# LEDs.net
KiCad netlist of a schematic drawn in Altium Designer
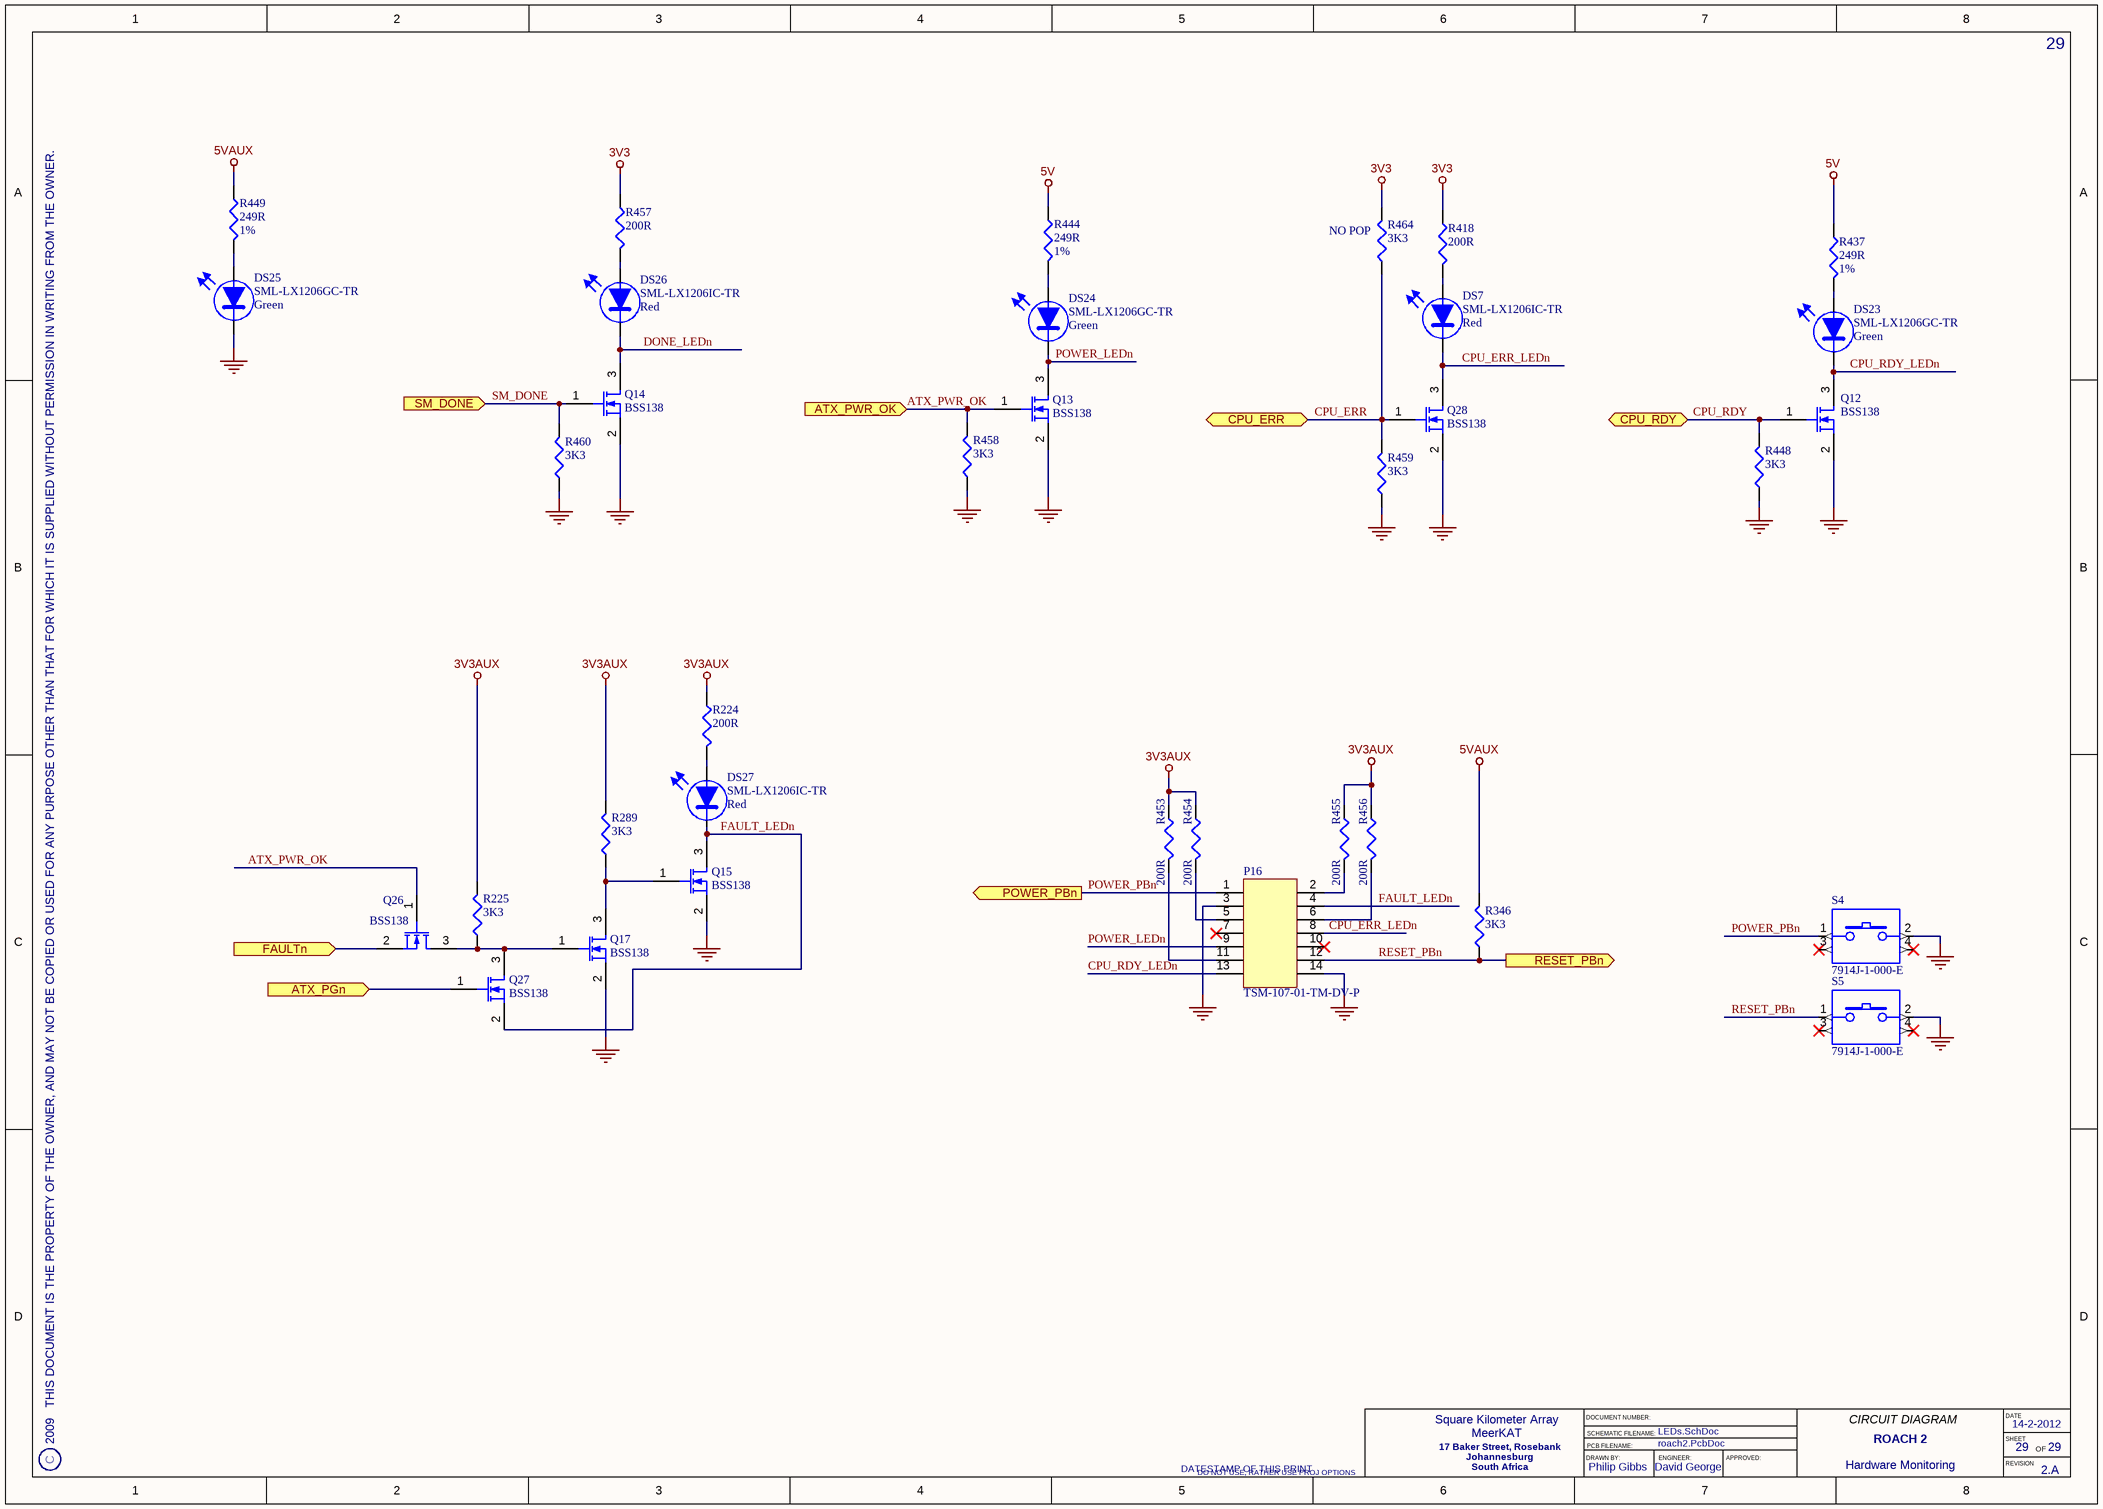
[diagram p0: LEDs.SchDoc]

(export (version "E")
  (design (tool "Eeschema 10.0.6"))
  (components
    (comp (ref "DS7")
      (value "SML-LX1206IC-TR")
      (footprint "LEDC3216X120N")
      (description "Red, Surface mount, LED, 1206")
      (fields (field (name "COLOUR") "Red") (field (name "MANUFACTURER") "LUMEX"))
      (libsource (lib "altium_db") (part "LEDSTD"))
    )
    (comp (ref "DS23")
      (value "SML-LX1206GC-TR")
      (footprint "LEDC3216X120N")
      (description "Green, Surface mount, LED, 1206")
      (fields (field (name "COLOUR") "Green") (field (name "MANUFACTURER") "LUMEX"))
      (libsource (lib "altium_db") (part "LEDSTD"))
    )
    (comp (ref "DS24")
      (value "SML-LX1206GC-TR")
      (footprint "LEDC3216X120N")
      (description "Green, Surface mount, LED, 1206")
      (fields (field (name "COLOUR") "Green") (field (name "MANUFACTURER") "LUMEX"))
      (libsource (lib "altium_db") (part "LEDSTD"))
    )
    (comp (ref "DS25")
      (value "SML-LX1206GC-TR")
      (footprint "LEDC3216X120N")
      (description "Green, Surface mount, LED, 1206")
      (fields (field (name "COLOUR") "Green") (field (name "MANUFACTURER") "LUMEX"))
      (libsource (lib "altium_db") (part "LEDSTD"))
    )
    (comp (ref "DS26")
      (value "SML-LX1206IC-TR")
      (footprint "LEDC3216X120N")
      (description "Red, Surface mount, LED, 1206")
      (fields (field (name "COLOUR") "Red") (field (name "MANUFACTURER") "LUMEX"))
      (libsource (lib "altium_db") (part "LEDSTD"))
    )
    (comp (ref "DS27")
      (value "SML-LX1206IC-TR")
      (footprint "LEDC3216X120N")
      (description "Red, Surface mount, LED, 1206")
      (fields (field (name "COLOUR") "Red") (field (name "MANUFACTURER") "LUMEX"))
      (libsource (lib "altium_db") (part "LEDSTD"))
    )
    (comp (ref "P16")
      (value "TSM-107-01-TM-DV-P")
      (footprint "SAMTEC_TSM-107-01-TM-DV-P")
      (description "2x7, 2.54 mm Pitch, Male Header")
      (fields (field (name "PARTNUM") "TSM-107-01-TM-DV-P") (field (name "MANUFACTURER") "SAMTEC"))
      (libsource (lib "altium_db") (part "con_hdr_2x7"))
    )
    (comp (ref "Q12")
      (value "BSS138")
      (footprint "SOT95P245X110-3N")
      (description "N-Channel Logic Level Enhancement Mode Field Effect Transistor")
      (fields (field (name "MANUFACTURER") "Fairchild Semiconductor"))
      (libsource (lib "altium_db") (part "BSS138"))
    )
    (comp (ref "Q13")
      (value "BSS138")
      (footprint "SOT95P245X110-3N")
      (description "N-Channel Logic Level Enhancement Mode Field Effect Transistor")
      (fields (field (name "MANUFACTURER") "Fairchild Semiconductor"))
      (libsource (lib "altium_db") (part "BSS138"))
    )
    (comp (ref "Q14")
      (value "BSS138")
      (footprint "SOT95P245X110-3N")
      (description "N-Channel Logic Level Enhancement Mode Field Effect Transistor")
      (fields (field (name "MANUFACTURER") "Fairchild Semiconductor"))
      (libsource (lib "altium_db") (part "BSS138"))
    )
    (comp (ref "Q15")
      (value "BSS138")
      (footprint "SOT95P245X110-3N")
      (description "N-Channel Logic Level Enhancement Mode Field Effect Transistor")
      (fields (field (name "MANUFACTURER") "Fairchild Semiconductor"))
      (libsource (lib "altium_db") (part "BSS138"))
    )
    (comp (ref "Q17")
      (value "BSS138")
      (footprint "SOT95P245X110-3N")
      (description "N-Channel Logic Level Enhancement Mode Field Effect Transistor")
      (fields (field (name "MANUFACTURER") "Fairchild Semiconductor"))
      (libsource (lib "altium_db") (part "BSS138"))
    )
    (comp (ref "Q26")
      (value "BSS138")
      (footprint "SOT95P245X110-3N")
      (description "N-Channel Logic Level Enhancement Mode Field Effect Transistor")
      (fields (field (name "MANUFACTURER") "Fairchild Semiconductor"))
      (libsource (lib "altium_db") (part "BSS138"))
    )
    (comp (ref "Q27")
      (value "BSS138")
      (footprint "SOT95P245X110-3N")
      (description "N-Channel Logic Level Enhancement Mode Field Effect Transistor")
      (fields (field (name "MANUFACTURER") "Fairchild Semiconductor"))
      (libsource (lib "altium_db") (part "BSS138"))
    )
    (comp (ref "Q28")
      (value "BSS138")
      (footprint "SOT95P245X110-3N")
      (description "N-Channel Logic Level Enhancement Mode Field Effect Transistor")
      (fields (field (name "MANUFACTURER") "Fairchild Semiconductor"))
      (libsource (lib "altium_db") (part "BSS138"))
    )
    (comp (ref "R224")
      (value "200R")
      (footprint "RESC1005X40L")
      (description "200R, 1.1mm x 0.5mm, Thick Film Resistor")
      (fields (field (name "MANUFACTURER") "ROYALOHM") (field (name "PARTNUM") "0402WGF0201T1E"))
      (libsource (lib "altium_db") (part "ResStd"))
    )
    (comp (ref "R225")
      (value "3K3")
      (footprint "RESC1005X40L")
      (description "3K3, 1.1mm x 0.5mm, Thick Film Resistor")
      (fields (field (name "MANUFACTURER") "ROYALOHM") (field (name "PARTNUM") "0402WGJ0332T1E"))
      (libsource (lib "altium_db") (part "ResStd"))
    )
    (comp (ref "R289")
      (value "3K3")
      (footprint "RESC1005X40L")
      (description "3K3, 1.1mm x 0.5mm, Thick Film Resistor")
      (fields (field (name "MANUFACTURER") "ROYALOHM") (field (name "PARTNUM") "0402WGJ0332T1E"))
      (libsource (lib "altium_db") (part "ResStd"))
    )
    (comp (ref "R346")
      (value "3K3")
      (footprint "RESC1005X40L")
      (description "3K3, 1.1mm x 0.5mm, Thick Film Resistor")
      (fields (field (name "MANUFACTURER") "ROYALOHM") (field (name "PARTNUM") "0402WGJ0332T1E"))
      (libsource (lib "altium_db") (part "ResStd"))
    )
    (comp (ref "R418")
      (value "200R")
      (footprint "RESC1005X40L")
      (description "200R, 1.1mm x 0.5mm, Thick Film Resistor")
      (fields (field (name "MANUFACTURER") "ROYALOHM") (field (name "PARTNUM") "0402WGF0201T1E"))
      (libsource (lib "altium_db") (part "ResStd"))
    )
    (comp (ref "R437")
      (value "249R")
      (footprint "RESC1005X40L")
      (description "249R, 1.1mm x 0.5mm, Thick Film Resistor")
      (fields
        (field (name "MANUFACTURER") "ROYALOHM")
        (field (name "PARTNUM") "0402WGF2490T1E")
        (field (name "TOLERANCE") "1%")
      )
      (libsource (lib "altium_db") (part "ResStd"))
    )
    (comp (ref "R444")
      (value "249R")
      (footprint "RESC1005X40L")
      (description "249R, 1.1mm x 0.5mm, Thick Film Resistor")
      (fields
        (field (name "MANUFACTURER") "ROYALOHM")
        (field (name "PARTNUM") "0402WGF2490T1E")
        (field (name "TOLERANCE") "1%")
      )
      (libsource (lib "altium_db") (part "ResStd"))
    )
    (comp (ref "R448")
      (value "3K3")
      (footprint "RESC1005X40L")
      (description "3K3, 1.1mm x 0.5mm, Thick Film Resistor")
      (fields (field (name "MANUFACTURER") "ROYALOHM") (field (name "PARTNUM") "0402WGJ0332T1E"))
      (libsource (lib "altium_db") (part "ResStd"))
    )
    (comp (ref "R449")
      (value "249R")
      (footprint "RESC1005X40L")
      (description "249R, 1.1mm x 0.5mm, Thick Film Resistor")
      (fields
        (field (name "MANUFACTURER") "ROYALOHM")
        (field (name "PARTNUM") "0402WGF2490T1E")
        (field (name "TOLERANCE") "1%")
      )
      (libsource (lib "altium_db") (part "ResStd"))
    )
    (comp (ref "R453")
      (value "200R")
      (footprint "RESC1005X40L")
      (description "200R, 1.1mm x 0.5mm, Thick Film Resistor")
      (fields (field (name "MANUFACTURER") "ROYALOHM") (field (name "PARTNUM") "0402WGF0201T1E"))
      (libsource (lib "altium_db") (part "ResStd"))
    )
    (comp (ref "R454")
      (value "200R")
      (footprint "RESC1005X40L")
      (description "200R, 1.1mm x 0.5mm, Thick Film Resistor")
      (fields (field (name "MANUFACTURER") "ROYALOHM") (field (name "PARTNUM") "0402WGF0201T1E"))
      (libsource (lib "altium_db") (part "ResStd"))
    )
    (comp (ref "R455")
      (value "200R")
      (footprint "RESC1005X40L")
      (description "200R, 1.1mm x 0.5mm, Thick Film Resistor")
      (fields (field (name "MANUFACTURER") "ROYALOHM") (field (name "PARTNUM") "0402WGF0201T1E"))
      (libsource (lib "altium_db") (part "ResStd"))
    )
    (comp (ref "R456")
      (value "200R")
      (footprint "RESC1005X40L")
      (description "200R, 1.1mm x 0.5mm, Thick Film Resistor")
      (fields (field (name "MANUFACTURER") "ROYALOHM") (field (name "PARTNUM") "0402WGF0201T1E"))
      (libsource (lib "altium_db") (part "ResStd"))
    )
    (comp (ref "R457")
      (value "200R")
      (footprint "RESC1005X40L")
      (description "200R, 1.1mm x 0.5mm, Thick Film Resistor")
      (fields (field (name "MANUFACTURER") "ROYALOHM") (field (name "PARTNUM") "0402WGF0201T1E"))
      (libsource (lib "altium_db") (part "ResStd"))
    )
    (comp (ref "R458")
      (value "3K3")
      (footprint "RESC1005X40L")
      (description "3K3, 1.1mm x 0.5mm, Thick Film Resistor")
      (fields (field (name "MANUFACTURER") "ROYALOHM") (field (name "PARTNUM") "0402WGJ0332T1E"))
      (libsource (lib "altium_db") (part "ResStd"))
    )
    (comp (ref "R459")
      (value "3K3")
      (footprint "RESC1005X40L")
      (description "3K3, 1.1mm x 0.5mm, Thick Film Resistor")
      (fields (field (name "MANUFACTURER") "ROYALOHM") (field (name "PARTNUM") "0402WGJ0332T1E"))
      (libsource (lib "altium_db") (part "ResStd"))
    )
    (comp (ref "R460")
      (value "3K3")
      (footprint "RESC1005X40L")
      (description "3K3, 1.1mm x 0.5mm, Thick Film Resistor")
      (fields (field (name "MANUFACTURER") "ROYALOHM") (field (name "PARTNUM") "0402WGJ0332T1E"))
      (libsource (lib "altium_db") (part "ResStd"))
    )
    (comp (ref "R464")
      (value "3K3")
      (footprint "RESC1005X40L")
      (description "3K3, 1.1mm x 0.5mm, Thick Film Resistor")
      (fields (field (name "MANUFACTURER") "ROYALOHM") (field (name "PARTNUM") "0402WGJ0332T1E"))
      (libsource (lib "altium_db") (part "ResStd"))
    )
    (comp (ref "S4")
      (value "7914J-1-000-E")
      (footprint "7914J-X-XXX-X")
      (description "4mm, Surface mount, Sealed Key Switch")
      (fields (field (name "PARTNUM") "7914J-1-000-E") (field (name "MANUFACTURER") "BOURNS"))
      (libsource (lib "altium_db") (part "7914X-X-XXX-X"))
    )
    (comp (ref "S5")
      (value "7914J-1-000-E")
      (footprint "7914J-X-XXX-X")
      (description "4mm, Surface mount, Sealed Key Switch")
      (fields (field (name "PARTNUM") "7914J-1-000-E") (field (name "MANUFACTURER") "BOURNS"))
      (libsource (lib "altium_db") (part "7914X-X-XXX-X"))
    )
  )
  (nets
    (net (code "1") (name "/ATX_PGn") (class "Default")
      (node (ref "Q27") (pin "1") (pinfunction "G_1") (pintype "passive"))
    )
    (net (code "2") (name "/ATX_PWR_OK") (class "Default")
      (node (ref "Q13") (pin "1") (pinfunction "G_1") (pintype "passive"))
      (node (ref "Q26") (pin "1") (pinfunction "G_1") (pintype "passive"))
      (node (ref "R458") (pin "2") (pinfunction "2_2") (pintype "passive"))
    )
    (net (code "3") (name "/CPU_ERR") (class "Default")
      (node (ref "Q28") (pin "1") (pinfunction "G_1") (pintype "passive"))
      (node (ref "R459") (pin "2") (pinfunction "2_2") (pintype "passive"))
      (node (ref "R464") (pin "1") (pinfunction "1_1") (pintype "passive"))
    )
    (net (code "4") (name "/CPU_ERR_LEDn") (class "Default")
      (node (ref "DS7") (pin "1") (pinfunction "K_1") (pintype "passive"))
      (node (ref "P16") (pin "8") (pinfunction "8_8") (pintype "passive"))
      (node (ref "Q28") (pin "3") (pinfunction "D_3") (pintype "passive"))
    )
    (net (code "5") (name "/CPU_RDY") (class "Default")
      (node (ref "Q12") (pin "1") (pinfunction "G_1") (pintype "passive"))
      (node (ref "R448") (pin "2") (pinfunction "2_2") (pintype "passive"))
    )
    (net (code "6") (name "/CPU_RDY_LEDn") (class "Default")
      (node (ref "DS23") (pin "1") (pinfunction "K_1") (pintype "passive"))
      (node (ref "P16") (pin "13") (pinfunction "13_13") (pintype "passive"))
      (node (ref "Q12") (pin "3") (pinfunction "D_3") (pintype "passive"))
    )
    (net (code "7") (name "/DONE_LEDn") (class "Default")
      (node (ref "DS26") (pin "1") (pinfunction "K_1") (pintype "passive"))
      (node (ref "Q14") (pin "3") (pinfunction "D_3") (pintype "passive"))
    )
    (net (code "8") (name "/FAULT_LEDn") (class "Default")
      (node (ref "DS27") (pin "1") (pinfunction "K_1") (pintype "passive"))
      (node (ref "P16") (pin "4") (pinfunction "4_4") (pintype "passive"))
      (node (ref "Q15") (pin "3") (pinfunction "D_3") (pintype "passive"))
      (node (ref "Q27") (pin "2") (pinfunction "S_2") (pintype "passive"))
    )
    (net (code "9") (name "/FAULTn") (class "Default")
      (node (ref "Q26") (pin "2") (pinfunction "S_2") (pintype "passive"))
    )
    (net (code "10") (name "/POWER_LEDn") (class "Default")
      (node (ref "DS24") (pin "1") (pinfunction "K_1") (pintype "passive"))
      (node (ref "P16") (pin "9") (pinfunction "9_9") (pintype "passive"))
      (node (ref "Q13") (pin "3") (pinfunction "D_3") (pintype "passive"))
    )
    (net (code "11") (name "/POWER_PBn") (class "Default")
      (node (ref "P16") (pin "1") (pinfunction "1_1") (pintype "passive"))
      (node (ref "S4") (pin "1") (pinfunction "1_1") (pintype "output"))
    )
    (net (code "12") (name "/RESET_PBn") (class "Default")
      (node (ref "P16") (pin "12") (pinfunction "12_12") (pintype "passive"))
      (node (ref "R346") (pin "1") (pinfunction "1_1") (pintype "passive"))
      (node (ref "S5") (pin "1") (pinfunction "1_1") (pintype "output"))
    )
    (net (code "13") (name "/SM_DONE") (class "Default")
      (node (ref "Q14") (pin "1") (pinfunction "G_1") (pintype "passive"))
      (node (ref "R460") (pin "2") (pinfunction "2_2") (pintype "passive"))
    )
    (net (code "14") (name "3V3") (class "Default")
      (node (ref "R418") (pin "1") (pinfunction "1_1") (pintype "passive"))
      (node (ref "R457") (pin "1") (pinfunction "1_1") (pintype "passive"))
      (node (ref "R464") (pin "2") (pinfunction "2_2") (pintype "passive"))
    )
    (net (code "15") (name "3V3AUX") (class "Default")
      (node (ref "R224") (pin "1") (pinfunction "1_1") (pintype "passive"))
      (node (ref "R225") (pin "2") (pinfunction "2_2") (pintype "passive"))
      (node (ref "R289") (pin "2") (pinfunction "2_2") (pintype "passive"))
      (node (ref "R453") (pin "1") (pinfunction "1_1") (pintype "passive"))
      (node (ref "R454") (pin "1") (pinfunction "1_1") (pintype "passive"))
      (node (ref "R455") (pin "1") (pinfunction "1_1") (pintype "passive"))
      (node (ref "R456") (pin "1") (pinfunction "1_1") (pintype "passive"))
    )
    (net (code "16") (name "5V") (class "Default")
      (node (ref "R437") (pin "1") (pinfunction "1_1") (pintype "passive"))
      (node (ref "R444") (pin "1") (pinfunction "1_1") (pintype "passive"))
    )
    (net (code "17") (name "5VAUX") (class "Default")
      (node (ref "R346") (pin "2") (pinfunction "2_2") (pintype "passive"))
      (node (ref "R449") (pin "1") (pinfunction "1_1") (pintype "passive"))
    )
    (net (code "18") (name "GND") (class "Default")
      (node (ref "DS25") (pin "1") (pinfunction "K_1") (pintype "passive"))
      (node (ref "P16") (pin "14") (pinfunction "14_14") (pintype "passive"))
      (node (ref "P16") (pin "3") (pinfunction "3_3") (pintype "passive"))
      (node (ref "Q12") (pin "2") (pinfunction "S_2") (pintype "passive"))
      (node (ref "Q13") (pin "2") (pinfunction "S_2") (pintype "passive"))
      (node (ref "Q14") (pin "2") (pinfunction "S_2") (pintype "passive"))
      (node (ref "Q15") (pin "2") (pinfunction "S_2") (pintype "passive"))
      (node (ref "Q17") (pin "2") (pinfunction "S_2") (pintype "passive"))
      (node (ref "Q28") (pin "2") (pinfunction "S_2") (pintype "passive"))
      (node (ref "R448") (pin "1") (pinfunction "1_1") (pintype "passive"))
      (node (ref "R458") (pin "1") (pinfunction "1_1") (pintype "passive"))
      (node (ref "R459") (pin "1") (pinfunction "1_1") (pintype "passive"))
      (node (ref "R460") (pin "1") (pinfunction "1_1") (pintype "passive"))
      (node (ref "S4") (pin "2") (pinfunction "2_2") (pintype "output"))
      (node (ref "S5") (pin "2") (pinfunction "2_2") (pintype "output"))
    )
    (net (code "19") (name "Net-(DS7-A)") (class "Default")
      (node (ref "DS7") (pin "2") (pinfunction "A_2") (pintype "passive"))
      (node (ref "R418") (pin "2") (pinfunction "2_2") (pintype "passive"))
    )
    (net (code "20") (name "Net-(DS23-A)") (class "Default")
      (node (ref "DS23") (pin "2") (pinfunction "A_2") (pintype "passive"))
      (node (ref "R437") (pin "2") (pinfunction "2_2") (pintype "passive"))
    )
    (net (code "21") (name "Net-(DS24-A)") (class "Default")
      (node (ref "DS24") (pin "2") (pinfunction "A_2") (pintype "passive"))
      (node (ref "R444") (pin "2") (pinfunction "2_2") (pintype "passive"))
    )
    (net (code "22") (name "Net-(DS25-A)") (class "Default")
      (node (ref "DS25") (pin "2") (pinfunction "A_2") (pintype "passive"))
      (node (ref "R449") (pin "2") (pinfunction "2_2") (pintype "passive"))
    )
    (net (code "23") (name "Net-(DS26-A)") (class "Default")
      (node (ref "DS26") (pin "2") (pinfunction "A_2") (pintype "passive"))
      (node (ref "R457") (pin "2") (pinfunction "2_2") (pintype "passive"))
    )
    (net (code "24") (name "Net-(DS27-A)") (class "Default")
      (node (ref "DS27") (pin "2") (pinfunction "A_2") (pintype "passive"))
      (node (ref "R224") (pin "2") (pinfunction "2_2") (pintype "passive"))
    )
    (net (code "25") (name "Net-(P16-Pad2)") (class "Default")
      (node (ref "P16") (pin "2") (pinfunction "2_2") (pintype "passive"))
      (node (ref "R455") (pin "2") (pinfunction "2_2") (pintype "passive"))
    )
    (net (code "26") (name "Net-(P16-Pad5)") (class "Default")
      (node (ref "P16") (pin "5") (pinfunction "5_5") (pintype "passive"))
      (node (ref "R454") (pin "2") (pinfunction "2_2") (pintype "passive"))
    )
    (net (code "27") (name "Net-(P16-Pad6)") (class "Default")
      (node (ref "P16") (pin "6") (pinfunction "6_6") (pintype "passive"))
      (node (ref "R456") (pin "2") (pinfunction "2_2") (pintype "passive"))
    )
    (net (code "28") (name "Net-(P16-Pad11)") (class "Default")
      (node (ref "P16") (pin "11") (pinfunction "11_11") (pintype "passive"))
      (node (ref "R453") (pin "2") (pinfunction "2_2") (pintype "passive"))
    )
    (net (code "29") (name "Net-(Q15-G)") (class "Default")
      (node (ref "Q15") (pin "1") (pinfunction "G_1") (pintype "passive"))
      (node (ref "Q17") (pin "3") (pinfunction "D_3") (pintype "passive"))
      (node (ref "R289") (pin "1") (pinfunction "1_1") (pintype "passive"))
    )
    (net (code "30") (name "Net-(Q17-G)") (class "Default")
      (node (ref "Q17") (pin "1") (pinfunction "G_1") (pintype "passive"))
      (node (ref "Q26") (pin "3") (pinfunction "D_3") (pintype "passive"))
      (node (ref "Q27") (pin "3") (pinfunction "D_3") (pintype "passive"))
      (node (ref "R225") (pin "1") (pinfunction "1_1") (pintype "passive"))
    )
    (net (code "31") (name "unconnected-(P16-Pad7)") (class "Default")
      (node (ref "P16") (pin "7") (pinfunction "7_7") (pintype "passive+no_connect"))
    )
    (net (code "32") (name "unconnected-(P16-Pad10)") (class "Default")
      (node (ref "P16") (pin "10") (pinfunction "10_10") (pintype "passive+no_connect"))
    )
    (net (code "33") (name "unconnected-(S4-Pad3)") (class "Default")
      (node (ref "S4") (pin "3") (pinfunction "3_3") (pintype "output+no_connect"))
    )
    (net (code "34") (name "unconnected-(S4-Pad4)") (class "Default")
      (node (ref "S4") (pin "4") (pinfunction "4_4") (pintype "output+no_connect"))
    )
    (net (code "35") (name "unconnected-(S5-Pad3)") (class "Default")
      (node (ref "S5") (pin "3") (pinfunction "3_3") (pintype "output+no_connect"))
    )
    (net (code "36") (name "unconnected-(S5-Pad4)") (class "Default")
      (node (ref "S5") (pin "4") (pinfunction "4_4") (pintype "output+no_connect"))
    )
  )
)
